# 12V_Buck_Converter.net
KiCad netlist of a schematic drawn in Altium Designer
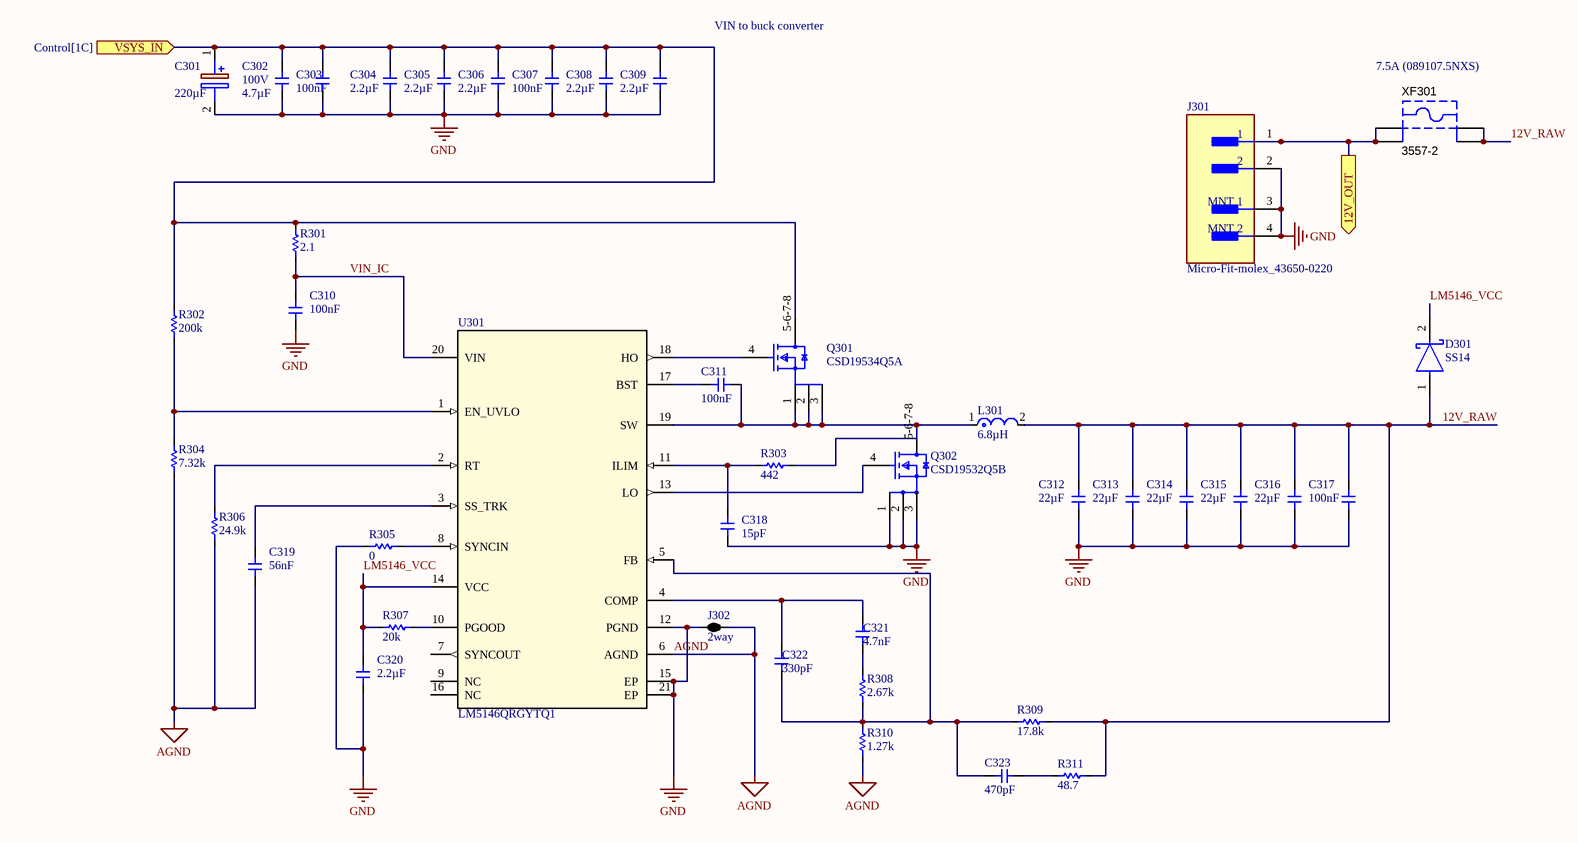
[diagram p0: 12V_Buck_Converter.SchDoc]

(export (version "E")
  (design (tool "Eeschema 10.0.6"))
  (components
    (comp (ref "C301")
      (value "220µF")
      (footprint "SamacSys:EEEFK0J103SM")
      (description "Capacitor Polarised")
      (fields
        (field (name "MANUFACTURER_PART_NUMBER") "EEV-FK2A221M")
        (field (name "MOUSER PART NUMBER") "667-EEV-FK2A221M")
      )
      (libsource (lib "*") (part "EEV-FK2A221M"))
    )
    (comp (ref "C302")
      (value "non-polar_Capacitor")
      (footprint "1210")
      (description "SMD type ceramic capacitor")
      (fields
        (field (name "VOLTAGE") "100V")
        (field (name "CAPACITANCE") "4.7µF")
        (field (name "SOURCE") "robit_passive.SchLib")
      )
      (libsource (lib "robit circuit") (part "Capacitor"))
    )
    (comp (ref "C303")
      (value "non-polar_Capacitor")
      (footprint "0603")
      (description "SMD type ceramic capacitor")
      (fields
        (field (name "VOLTAGE") "100V")
        (field (name "CAPACITANCE") "100nF")
        (field (name "SOURCE") "robit_passive.SchLib")
      )
      (libsource (lib "robit circuit") (part "Capacitor"))
    )
    (comp (ref "C304")
      (value "non-polar_Capacitor")
      (footprint "1210")
      (description "SMD type ceramic capacitor")
      (fields
        (field (name "VOLTAGE") "50V")
        (field (name "CAPACITANCE") "2.2µF")
        (field (name "SOURCE") "robit_passive.SchLib")
      )
      (libsource (lib "robit circuit") (part "Capacitor"))
    )
    (comp (ref "C305")
      (value "non-polar_Capacitor")
      (footprint "1210")
      (description "SMD type ceramic capacitor")
      (fields
        (field (name "VOLTAGE") "50V")
        (field (name "CAPACITANCE") "2.2µF")
        (field (name "SOURCE") "robit_passive.SchLib")
      )
      (libsource (lib "robit circuit") (part "Capacitor"))
    )
    (comp (ref "C306")
      (value "non-polar_Capacitor")
      (footprint "0603")
      (description "SMD type ceramic capacitor")
      (fields
        (field (name "VOLTAGE") "50V")
        (field (name "CAPACITANCE") "2.2µF")
        (field (name "SOURCE") "robit_passive.SchLib")
      )
      (libsource (lib "robit circuit") (part "Capacitor"))
    )
    (comp (ref "C307")
      (value "non-polar_Capacitor")
      (footprint "0603")
      (description "SMD type ceramic capacitor")
      (fields
        (field (name "VOLTAGE") "50V")
        (field (name "CAPACITANCE") "100nF")
        (field (name "SOURCE") "robit_passive.SchLib")
      )
      (libsource (lib "robit circuit") (part "Capacitor"))
    )
    (comp (ref "C308")
      (value "non-polar_Capacitor")
      (footprint "1210")
      (description "SMD type ceramic capacitor")
      (fields
        (field (name "VOLTAGE") "50V")
        (field (name "CAPACITANCE") "2.2µF")
        (field (name "SOURCE") "robit_passive.SchLib")
      )
      (libsource (lib "robit circuit") (part "Capacitor"))
    )
    (comp (ref "C309")
      (value "non-polar_Capacitor")
      (footprint "1210")
      (description "SMD type ceramic capacitor")
      (fields
        (field (name "VOLTAGE") "50V")
        (field (name "CAPACITANCE") "2.2µF")
        (field (name "SOURCE") "robit_passive.SchLib")
      )
      (libsource (lib "robit circuit") (part "Capacitor"))
    )
    (comp (ref "C310")
      (value "non-polar_Capacitor")
      (footprint "0603")
      (description "SMD type ceramic capacitor")
      (fields
        (field (name "VOLTAGE") "50V")
        (field (name "CAPACITANCE") "100nF")
        (field (name "SOURCE") "robit_passive.SchLib")
      )
      (libsource (lib "robit circuit") (part "Capacitor"))
    )
    (comp (ref "C311")
      (value "non-polar_Capacitor")
      (footprint "0603")
      (description "SMD type ceramic capacitor")
      (fields
        (field (name "VOLTAGE") "50V")
        (field (name "CAPACITANCE") "100nF")
        (field (name "SOURCE") "robit_passive.SchLib")
      )
      (libsource (lib "robit circuit") (part "Capacitor"))
    )
    (comp (ref "C312")
      (value "non-polar_Capacitor")
      (footprint "1210")
      (description "SMD type ceramic capacitor")
      (fields
        (field (name "VOLTAGE") "50V")
        (field (name "CAPACITANCE") "22µF")
        (field (name "SOURCE") "robit_passive.SchLib")
      )
      (libsource (lib "robit circuit") (part "Capacitor"))
    )
    (comp (ref "C313")
      (value "non-polar_Capacitor")
      (footprint "1210")
      (description "SMD type ceramic capacitor")
      (fields
        (field (name "VOLTAGE") "50V")
        (field (name "CAPACITANCE") "22µF")
        (field (name "SOURCE") "robit_passive.SchLib")
      )
      (libsource (lib "robit circuit") (part "Capacitor"))
    )
    (comp (ref "C314")
      (value "non-polar_Capacitor")
      (footprint "1210")
      (description "SMD type ceramic capacitor")
      (fields
        (field (name "VOLTAGE") "50V")
        (field (name "CAPACITANCE") "22µF")
        (field (name "SOURCE") "robit_passive.SchLib")
      )
      (libsource (lib "robit circuit") (part "Capacitor"))
    )
    (comp (ref "C315")
      (value "non-polar_Capacitor")
      (footprint "1210")
      (description "SMD type ceramic capacitor")
      (fields
        (field (name "VOLTAGE") "50V")
        (field (name "CAPACITANCE") "22µF")
        (field (name "SOURCE") "robit_passive.SchLib")
      )
      (libsource (lib "robit circuit") (part "Capacitor"))
    )
    (comp (ref "C316")
      (value "non-polar_Capacitor")
      (footprint "1210")
      (description "SMD type ceramic capacitor")
      (fields
        (field (name "VOLTAGE") "50V")
        (field (name "CAPACITANCE") "22µF")
        (field (name "SOURCE") "robit_passive.SchLib")
      )
      (libsource (lib "robit circuit") (part "Capacitor"))
    )
    (comp (ref "C317")
      (value "non-polar_Capacitor")
      (footprint "0603")
      (description "SMD type ceramic capacitor")
      (fields
        (field (name "VOLTAGE") "100V")
        (field (name "CAPACITANCE") "100nF")
        (field (name "SOURCE") "robit_passive.SchLib")
      )
      (libsource (lib "robit circuit") (part "Capacitor"))
    )
    (comp (ref "C318")
      (value "non-polar_Capacitor")
      (footprint "0603")
      (description "SMD type ceramic capacitor")
      (fields
        (field (name "VOLTAGE") "50V")
        (field (name "CAPACITANCE") "15pF")
        (field (name "SOURCE") "robit_passive.SchLib")
      )
      (libsource (lib "robit circuit") (part "Capacitor"))
    )
    (comp (ref "C319")
      (value "non-polar_Capacitor")
      (footprint "0603")
      (description "SMD type ceramic capacitor")
      (fields
        (field (name "VOLTAGE") "50V")
        (field (name "CAPACITANCE") "56nF")
        (field (name "SOURCE") "robit_passive.SchLib")
      )
      (libsource (lib "robit circuit") (part "Capacitor"))
    )
    (comp (ref "C320")
      (value "non-polar_Capacitor")
      (footprint "1206")
      (description "SMD type ceramic capacitor")
      (fields
        (field (name "VOLTAGE") "50V")
        (field (name "CAPACITANCE") "2.2µF")
        (field (name "SOURCE") "robit_passive.SchLib")
      )
      (libsource (lib "robit circuit") (part "Capacitor"))
    )
    (comp (ref "C321")
      (value "non-polar_Capacitor")
      (footprint "0603")
      (description "SMD type ceramic capacitor")
      (fields
        (field (name "VOLTAGE") "50V")
        (field (name "CAPACITANCE") "4.7nF")
        (field (name "SOURCE") "robit_passive.SchLib")
      )
      (libsource (lib "robit circuit") (part "Capacitor"))
    )
    (comp (ref "C322")
      (value "non-polar_Capacitor")
      (footprint "0603")
      (description "SMD type ceramic capacitor")
      (fields
        (field (name "VOLTAGE") "50V")
        (field (name "CAPACITANCE") "330pF")
        (field (name "SOURCE") "robit_passive.SchLib")
      )
      (libsource (lib "robit circuit") (part "Capacitor"))
    )
    (comp (ref "C323")
      (value "non-polar_Capacitor")
      (footprint "0603")
      (description "SMD type ceramic capacitor")
      (fields
        (field (name "VOLTAGE") "50V")
        (field (name "CAPACITANCE") "470pF")
        (field (name "SOURCE") "robit_passive.SchLib")
      )
      (libsource (lib "robit circuit") (part "Capacitor"))
    )
    (comp (ref "D301")
      (value "SS14")
      (footprint "FP-403AE-MFG")
      (description "DIODE SCHOTTKY 40V 1A SMA")
      (fields
        (field (name "MANUFACTURER") "ON Semiconductor")
        (field (name "OCTOPART") "https://octopart.com/ss14-on+semiconductor-29205033")
      )
      (libsource (lib "Altium Content Vault") (part "360ad2f4ac25a952324d13796385471"))
    )
    (comp (ref "J301")
      (value "Micro-Fit-molex_43650-0220")
      (footprint "FP-43650-0220-MFG")
      (description "Rectangular Power Connector, 2 Contact(s), Male, Solder Terminal, Plug")
      (libsource (lib "robit circuit") (part "56ec3178a87b3978bdc1b3682cd516a"))
    )
    (comp (ref "J302")
      (value "2way")
      (footprint "2way_LP")
      (description "2 way net tie junction")
      (libsource (lib "robit circuit") (part "2way"))
    )
    (comp (ref "L301")
      (value "XAL1010")
      (footprint "FP-XAL1010-MFG")
      (description "General Purpose Inductor, 5.6uH, 20%, 1 Element, Composite-Core, SMD, 4539")
      (fields (field (name "INDUCTANCE") "6.8µH"))
      (libsource (lib "robit circuit") (part "4cc4b267dca4c8e51f7102f422741d8"))
    )
    (comp (ref "Q301")
      (value "CSD19534Q5A")
      (footprint "FP-DQJ0008A-MFG")
      (description "MOSFET N-CH 100V 50 8SON")
      (fields
        (field (name "OCTOPART") "https://octopart.com/csd19534q5a-texas+instruments-46749514")
        (field (name "MANUFACTURER") "Texas Instruments")
      )
      (libsource (lib "Altium Content Vault") (part "372bcbff2a0099001efc4acc0eb9b45"))
    )
    (comp (ref "Q302")
      (value "CSD19532Q5B")
      (footprint "FP-DNK0008A-MFG")
      (description "100-V, N channel NexFET™ power MOSFET, single SON 5 mm x 6 mm, 4.9 mOhm 8-VSON-CLIP -55 to 150")
      (libsource (lib "robit circuit") (part "6fb2c024a3b9031f6d89538bc87a0fd"))
    )
    (comp (ref "R301")
      (value "Resistor")
      (footprint "0603")
      (description "SMD type resistor")
      (fields (field (name "RESISTANCE") "2.1") (field (name "SOURCE") "robit_passive.SchLib"))
      (libsource (lib "robit circuit") (part "Resistor"))
    )
    (comp (ref "R302")
      (value "Resistor")
      (footprint "0603")
      (description "SMD type resistor")
      (fields (field (name "RESISTANCE") "200k") (field (name "SOURCE") "robit_passive.SchLib"))
      (libsource (lib "robit circuit") (part "Resistor"))
    )
    (comp (ref "R303")
      (value "Resistor")
      (footprint "0805")
      (description "SMD type resistor")
      (fields (field (name "RESISTANCE") "442") (field (name "SOURCE") "robit_passive.SchLib"))
      (libsource (lib "robit circuit") (part "Resistor"))
    )
    (comp (ref "R304")
      (value "Resistor")
      (footprint "0603")
      (description "SMD type resistor")
      (fields (field (name "RESISTANCE") "7.32k") (field (name "SOURCE") "robit_passive.SchLib"))
      (libsource (lib "robit circuit") (part "Resistor"))
    )
    (comp (ref "R305")
      (value "Resistor")
      (footprint "0603")
      (description "SMD type resistor")
      (fields (field (name "RESISTANCE") "0") (field (name "SOURCE") "robit_passive.SchLib"))
      (libsource (lib "robit circuit") (part "Resistor"))
    )
    (comp (ref "R306")
      (value "Resistor")
      (footprint "0603")
      (description "SMD type resistor")
      (fields (field (name "RESISTANCE") "24.9k") (field (name "SOURCE") "robit_passive.SchLib"))
      (libsource (lib "robit circuit") (part "Resistor"))
    )
    (comp (ref "R307")
      (value "Resistor")
      (footprint "0603")
      (description "SMD type resistor")
      (fields (field (name "RESISTANCE") "20k") (field (name "SOURCE") "robit_passive.SchLib"))
      (libsource (lib "robit circuit") (part "Resistor"))
    )
    (comp (ref "R308")
      (value "Resistor")
      (footprint "0603")
      (description "SMD type resistor")
      (fields (field (name "RESISTANCE") "2.67k") (field (name "SOURCE") "robit_passive.SchLib"))
      (libsource (lib "robit circuit") (part "Resistor"))
    )
    (comp (ref "R309")
      (value "Resistor")
      (footprint "0603")
      (description "SMD type resistor")
      (fields (field (name "RESISTANCE") "17.8k") (field (name "SOURCE") "robit_passive.SchLib"))
      (libsource (lib "robit circuit") (part "Resistor"))
    )
    (comp (ref "R310")
      (value "Resistor")
      (footprint "0603")
      (description "SMD type resistor")
      (fields (field (name "RESISTANCE") "1.27k") (field (name "SOURCE") "robit_passive.SchLib"))
      (libsource (lib "robit circuit") (part "Resistor"))
    )
    (comp (ref "R311")
      (value "Resistor")
      (footprint "0603")
      (description "SMD type resistor")
      (fields (field (name "RESISTANCE") "48.7") (field (name "SOURCE") "robit_passive.SchLib"))
      (libsource (lib "robit circuit") (part "Resistor"))
    )
    (comp (ref "U301")
      (value "LM5146QRGYTQ1")
      (footprint "RGY0020B")
      (description "Automotive 100-V synchronous buck DC/DC controller with wide duty-cycle range 20-VQFN -40 to 150")
      (fields (field (name "COPYRIGHT") "Copyright (C) 2026 Ultra Librarian. All rights reserved."))
      (libsource (lib "LM5146QRGYTQ1") (part "LM5146QRGYTQ1"))
    )
    (comp (ref "XF301")
      (value "3557-2")
      (footprint "KSTN-3557-2")
      (description "FUSE HOLDER, PCB MOUNT, 500VAC, 20A, ROHS")
      (fields (field (name "VOLTAGE") "500V") (field (name "MANUFACTURER") "Keystone-Electronics"))
      (libsource (lib "Altium Content Vault") (part "FUSE_HOLDER-4"))
    )
  )
  (nets
    (net (code "1") (name "/12V_OUT") (class "Default")
      (node (ref "J301") (pin "1") (pinfunction "1_1") (pintype "passive"))
      (node (ref "XF301") (pin "1") (pinfunction "1_1") (pintype "passive"))
      (node (ref "XF301") (pin "2") (pinfunction "2_2") (pintype "passive"))
    )
    (net (code "2") (name "/12V_RAW") (class "Default")
      (node (ref "C312") (pin "2") (pinfunction "2_2") (pintype "passive"))
      (node (ref "C313") (pin "2") (pinfunction "2_2") (pintype "passive"))
      (node (ref "C314") (pin "2") (pinfunction "2_2") (pintype "passive"))
      (node (ref "C315") (pin "2") (pinfunction "2_2") (pintype "passive"))
      (node (ref "C316") (pin "2") (pinfunction "2_2") (pintype "passive"))
      (node (ref "C317") (pin "2") (pinfunction "2_2") (pintype "passive"))
      (node (ref "D301") (pin "1") (pinfunction "A_1") (pintype "passive"))
      (node (ref "L301") (pin "2") (pinfunction "2_2") (pintype "passive"))
      (node (ref "R309") (pin "1") (pinfunction "1_1") (pintype "passive"))
      (node (ref "R311") (pin "1") (pinfunction "1_1") (pintype "passive"))
      (node (ref "XF301") (pin "3") (pinfunction "3_3") (pintype "passive"))
      (node (ref "XF301") (pin "4") (pinfunction "4_4") (pintype "passive"))
    )
    (net (code "3") (name "/LM5146_VCC") (class "Default")
      (node (ref "C320") (pin "2") (pinfunction "2_2") (pintype "passive"))
      (node (ref "D301") (pin "2") (pinfunction "C_2") (pintype "passive"))
      (node (ref "R307") (pin "2") (pinfunction "2_2") (pintype "passive"))
      (node (ref "U301") (pin "14") (pinfunction "VCC_14") (pintype "power_in"))
    )
    (net (code "4") (name "/VIN_IC") (class "Default")
      (node (ref "C310") (pin "2") (pinfunction "2_2") (pintype "passive"))
      (node (ref "R301") (pin "1") (pinfunction "1_1") (pintype "passive"))
      (node (ref "U301") (pin "20") (pinfunction "VIN_20") (pintype "power_in"))
    )
    (net (code "5") (name "/VSYS_IN") (class "Default")
      (node (ref "C301") (pin "1") (pinfunction "+_1") (pintype "passive"))
      (node (ref "C302") (pin "2") (pinfunction "2_2") (pintype "passive"))
      (node (ref "C303") (pin "2") (pinfunction "2_2") (pintype "passive"))
      (node (ref "C304") (pin "2") (pinfunction "2_2") (pintype "passive"))
      (node (ref "C305") (pin "2") (pinfunction "2_2") (pintype "passive"))
      (node (ref "C306") (pin "2") (pinfunction "2_2") (pintype "passive"))
      (node (ref "C307") (pin "2") (pinfunction "2_2") (pintype "passive"))
      (node (ref "C308") (pin "2") (pinfunction "2_2") (pintype "passive"))
      (node (ref "C309") (pin "2") (pinfunction "2_2") (pintype "passive"))
      (node (ref "Q301") (pin "5-6-7-8") (pinfunction "D_5-6-7-8") (pintype "passive"))
      (node (ref "R301") (pin "2") (pinfunction "2_2") (pintype "passive"))
      (node (ref "R302") (pin "2") (pinfunction "2_2") (pintype "passive"))
    )
    (net (code "6") (name "AGND") (class "Default")
      (node (ref "C319") (pin "1") (pinfunction "1_1") (pintype "passive"))
      (node (ref "J302") (pin "2") (pinfunction "2_2") (pintype "passive"))
      (node (ref "R304") (pin "1") (pinfunction "1_1") (pintype "passive"))
      (node (ref "R306") (pin "1") (pinfunction "1_1") (pintype "passive"))
      (node (ref "R310") (pin "2") (pinfunction "2_2") (pintype "passive"))
      (node (ref "U301") (pin "6") (pinfunction "AGND_6") (pintype "power_in"))
    )
    (net (code "7") (name "GND") (class "Default")
      (node (ref "C301") (pin "2") (pinfunction "-_2") (pintype "passive"))
      (node (ref "C302") (pin "1") (pinfunction "1_1") (pintype "passive"))
      (node (ref "C303") (pin "1") (pinfunction "1_1") (pintype "passive"))
      (node (ref "C304") (pin "1") (pinfunction "1_1") (pintype "passive"))
      (node (ref "C305") (pin "1") (pinfunction "1_1") (pintype "passive"))
      (node (ref "C306") (pin "1") (pinfunction "1_1") (pintype "passive"))
      (node (ref "C307") (pin "1") (pinfunction "1_1") (pintype "passive"))
      (node (ref "C308") (pin "1") (pinfunction "1_1") (pintype "passive"))
      (node (ref "C309") (pin "1") (pinfunction "1_1") (pintype "passive"))
      (node (ref "C310") (pin "1") (pinfunction "1_1") (pintype "passive"))
      (node (ref "C312") (pin "1") (pinfunction "1_1") (pintype "passive"))
      (node (ref "C313") (pin "1") (pinfunction "1_1") (pintype "passive"))
      (node (ref "C314") (pin "1") (pinfunction "1_1") (pintype "passive"))
      (node (ref "C315") (pin "1") (pinfunction "1_1") (pintype "passive"))
      (node (ref "C316") (pin "1") (pinfunction "1_1") (pintype "passive"))
      (node (ref "C317") (pin "1") (pinfunction "1_1") (pintype "passive"))
      (node (ref "C318") (pin "2") (pinfunction "2_2") (pintype "passive"))
      (node (ref "C320") (pin "1") (pinfunction "1_1") (pintype "passive"))
      (node (ref "J301") (pin "2") (pinfunction "2_2") (pintype "passive"))
      (node (ref "J301") (pin "3") (pinfunction "MNT_1_3") (pintype "passive"))
      (node (ref "J301") (pin "4") (pinfunction "MNT_2_4") (pintype "passive"))
      (node (ref "J302") (pin "1") (pinfunction "1_1") (pintype "passive"))
      (node (ref "Q302") (pin "1") (pinfunction "S_1") (pintype "passive"))
      (node (ref "Q302") (pin "2") (pinfunction "S_2") (pintype "passive"))
      (node (ref "Q302") (pin "3") (pinfunction "S_3") (pintype "passive"))
      (node (ref "R305") (pin "1") (pinfunction "1_1") (pintype "passive"))
      (node (ref "U301") (pin "12") (pinfunction "PGND_12") (pintype "power_in"))
      (node (ref "U301") (pin "15") (pinfunction "EP_15") (pintype "power_in"))
      (node (ref "U301") (pin "21") (pinfunction "EP_21") (pintype "power_in"))
    )
    (net (code "8") (name "Net-(C321-Pad1)") (class "Default")
      (node (ref "C321") (pin "1") (pinfunction "1_1") (pintype "passive"))
      (node (ref "R308") (pin "2") (pinfunction "2_2") (pintype "passive"))
    )
    (net (code "9") (name "Net-(C323-Pad1)") (class "Default")
      (node (ref "C323") (pin "1") (pinfunction "1_1") (pintype "passive"))
      (node (ref "R311") (pin "2") (pinfunction "2_2") (pintype "passive"))
    )
    (net (code "10") (name "Net-(Q301-G)") (class "Default")
      (node (ref "Q301") (pin "4") (pinfunction "G_4") (pintype "passive"))
      (node (ref "U301") (pin "18") (pinfunction "HO_18") (pintype "output"))
    )
    (net (code "11") (name "Net-(Q302-D)") (class "Default")
      (node (ref "C311") (pin "1") (pinfunction "1_1") (pintype "passive"))
      (node (ref "L301") (pin "1") (pinfunction "1_1") (pintype "passive"))
      (node (ref "Q301") (pin "1") (pinfunction "S_1") (pintype "passive"))
      (node (ref "Q301") (pin "2") (pinfunction "S_2") (pintype "passive"))
      (node (ref "Q301") (pin "3") (pinfunction "S_3") (pintype "passive"))
      (node (ref "Q302") (pin "5-6-7-8") (pinfunction "D_5-6-7-8") (pintype "passive"))
      (node (ref "R303") (pin "2") (pinfunction "2_2") (pintype "passive"))
      (node (ref "U301") (pin "19") (pinfunction "SW_19") (pintype "power_in"))
    )
    (net (code "12") (name "Net-(Q302-G)") (class "Default")
      (node (ref "Q302") (pin "4") (pinfunction "G_4") (pintype "passive"))
      (node (ref "U301") (pin "13") (pinfunction "LO_13") (pintype "output"))
    )
    (net (code "13") (name "Net-(U301-BST)") (class "Default")
      (node (ref "C311") (pin "2") (pinfunction "2_2") (pintype "passive"))
      (node (ref "U301") (pin "17") (pinfunction "BST_17") (pintype "passive"))
    )
    (net (code "14") (name "Net-(U301-COMP)") (class "Default")
      (node (ref "C321") (pin "2") (pinfunction "2_2") (pintype "passive"))
      (node (ref "C322") (pin "2") (pinfunction "2_2") (pintype "passive"))
      (node (ref "U301") (pin "4") (pinfunction "COMP_4") (pintype "passive"))
    )
    (net (code "15") (name "Net-(U301-EN_UVLO)") (class "Default")
      (node (ref "R302") (pin "1") (pinfunction "1_1") (pintype "passive"))
      (node (ref "R304") (pin "2") (pinfunction "2_2") (pintype "passive"))
      (node (ref "U301") (pin "1") (pinfunction "EN_UVLO_1") (pintype "input"))
    )
    (net (code "16") (name "Net-(U301-FB)") (class "Default")
      (node (ref "C322") (pin "1") (pinfunction "1_1") (pintype "passive"))
      (node (ref "C323") (pin "2") (pinfunction "2_2") (pintype "passive"))
      (node (ref "R308") (pin "1") (pinfunction "1_1") (pintype "passive"))
      (node (ref "R309") (pin "2") (pinfunction "2_2") (pintype "passive"))
      (node (ref "R310") (pin "1") (pinfunction "1_1") (pintype "passive"))
      (node (ref "U301") (pin "5") (pinfunction "FB_5") (pintype "input"))
    )
    (net (code "17") (name "Net-(U301-ILIM)") (class "Default")
      (node (ref "C318") (pin "1") (pinfunction "1_1") (pintype "passive"))
      (node (ref "R303") (pin "1") (pinfunction "1_1") (pintype "passive"))
      (node (ref "U301") (pin "11") (pinfunction "ILIM_11") (pintype "input"))
    )
    (net (code "18") (name "Net-(U301-PGOOD)") (class "Default")
      (node (ref "R307") (pin "1") (pinfunction "1_1") (pintype "passive"))
      (node (ref "U301") (pin "10") (pinfunction "PGOOD_10") (pintype "open_collector"))
    )
    (net (code "19") (name "Net-(U301-RT)") (class "Default")
      (node (ref "R306") (pin "2") (pinfunction "2_2") (pintype "passive"))
      (node (ref "U301") (pin "2") (pinfunction "RT_2") (pintype "input"))
    )
    (net (code "20") (name "Net-(U301-SS_TRK)") (class "Default")
      (node (ref "C319") (pin "2") (pinfunction "2_2") (pintype "passive"))
      (node (ref "U301") (pin "3") (pinfunction "SS_TRK_3") (pintype "input"))
    )
    (net (code "21") (name "Net-(U301-SYNCIN)") (class "Default")
      (node (ref "R305") (pin "2") (pinfunction "2_2") (pintype "passive"))
      (node (ref "U301") (pin "8") (pinfunction "SYNCIN_8") (pintype "input"))
    )
    (net (code "22") (name "unconnected-(U301-NC-Pad9)") (class "Default")
      (node (ref "U301") (pin "9") (pinfunction "NC_9") (pintype "passive"))
    )
    (net (code "23") (name "unconnected-(U301-NC-Pad16)") (class "Default")
      (node (ref "U301") (pin "16") (pinfunction "NC_16") (pintype "passive"))
    )
    (net (code "24") (name "unconnected-(U301-SYNCOUT-Pad7)") (class "Default")
      (node (ref "U301") (pin "7") (pinfunction "SYNCOUT_7") (pintype "output"))
    )
  )
)
